# Power_Distribution_2021_9V.net
KiCad netlist of a schematic drawn in Altium Designer
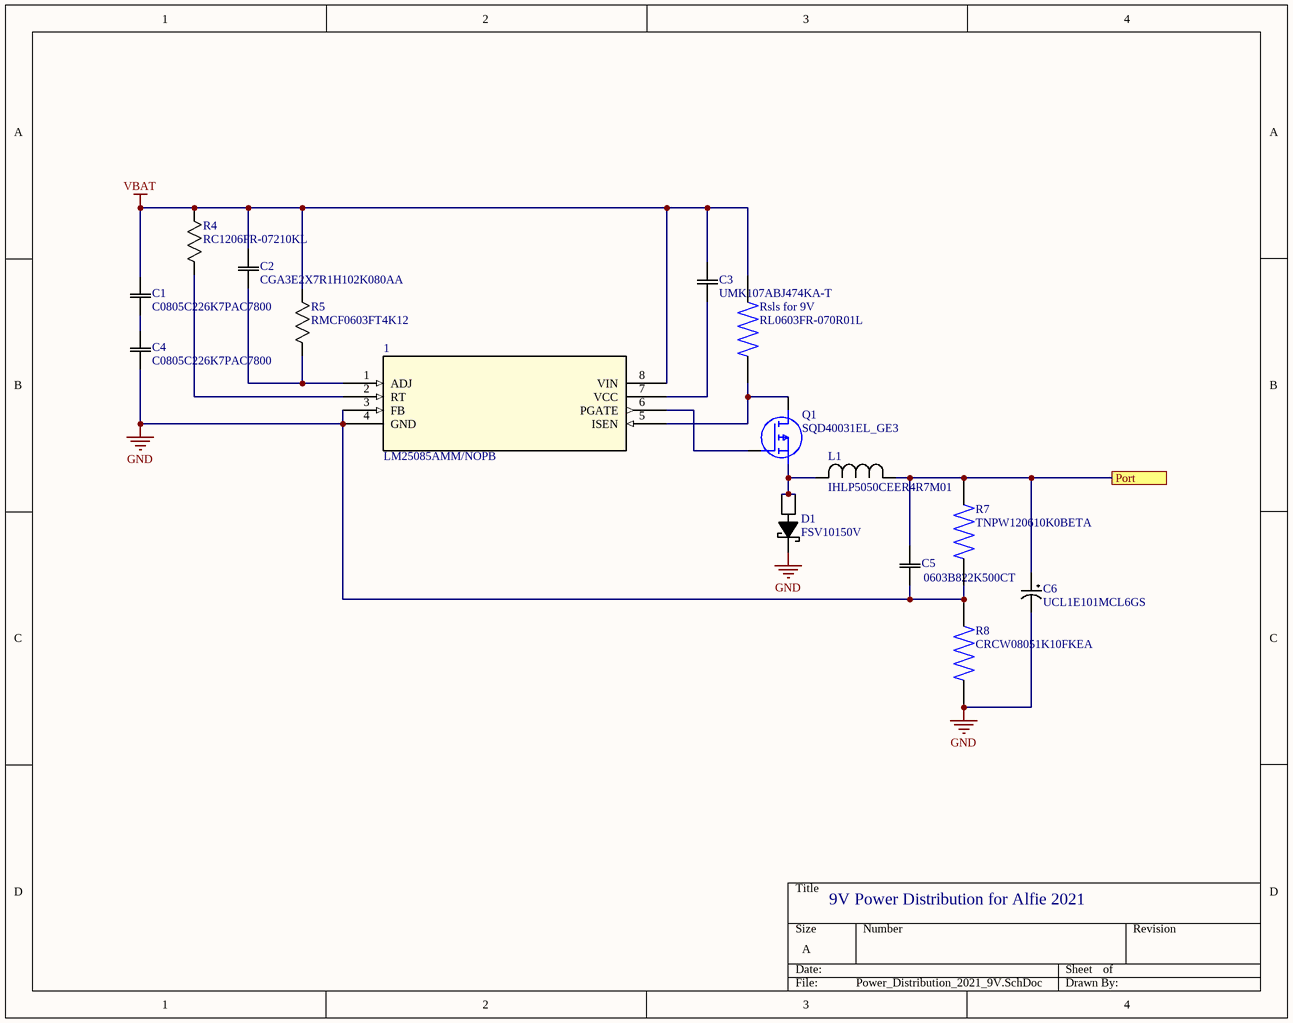
[diagram p0: Power_Distribution_2021_9V.SchDoc]

(export (version "E")
  (design (tool "Eeschema 10.0.6"))
  (components
    (comp (ref "1")
      (value "LM25085AMM/NOPB")
      (footprint "MUA08A")
      (description "IC REG CTRLR BUCK 8VSSOP")
      (fields (field (name "COPYRIGHT") "Copyright (C) 2021 Accelerated Designs. All rights reserved"))
      (libsource (lib "Power_Distribution") (part "LM25085AMM/NOPB"))
    )
    (comp (ref "C1")
      (value "C0805C226K7PAC7800")
      (footprint "SnapEDApcb:CAPC2012X140N")
      (description "22µF ±10% 4V Ceramic Capacitor X5R 0805 _2012 Metric")
      (fields (field (name "MF") "KEMET"))
      (libsource (lib "Power_Distribution") (part "C0805C226K7PAC7800"))
    )
    (comp (ref "C2")
      (value "CGA3E2X7R1H102K080AA")
      (footprint "CAP_1608_TDK")
      (description "CAP CER 1000PF 50V X7R 0603")
      (fields (field (name "COPYRIGHT") "Copyright (C) 2021 Accelerated Designs. All rights reserved"))
      (libsource (lib "Power_Distribution") (part "CGA3E2X7R1H102K080AA"))
    )
    (comp (ref "C3")
      (value "UMK107ABJ474KA-T")
      (footprint "cap_UMK107ABJ474KA-T_TAY")
      (description "CAP CER 0.47UF 50V X5R 0603")
      (fields (field (name "COPYRIGHT") "Copyright (C) 2018 Accelerated Designs. All rights reserved"))
      (libsource (lib "Power_Distribution") (part "UMK107ABJ474KA-T"))
    )
    (comp (ref "C4")
      (value "C0805C226K7PAC7800")
      (footprint "SnapEDApcb:CAPC2012X140N")
      (description "22µF ±10% 4V Ceramic Capacitor X5R 0805 _2012 Metric")
      (fields (field (name "MF") "KEMET"))
      (libsource (lib "Power_Distribution") (part "C0805C226K7PAC7800"))
    )
    (comp (ref "C5")
      (value "0603B822K500CT")
      (footprint "CAP_0603_S_WAL")
      (description "CAP CER 8200PF 50V X7R 0603")
      (fields (field (name "COPYRIGHT") "Copyright (C) 2021 Accelerated Designs. All rights reserved"))
      (libsource (lib "Power_Distribution") (part "0603B822K500CT"))
    )
    (comp (ref "C6")
      (value "UCL1E101MCL6GS")
      (footprint "U2-O_NCH")
      (description "CAP ALUM 100UF 20% 25V SMD")
      (fields (field (name "COPYRIGHT") "Copyright (C) 2021 Accelerated Designs. All rights reserved"))
      (libsource (lib "Power_Distribution") (part "UCL1E101MCL6GS"))
    )
    (comp (ref "D1")
      (value "FSV10150V")
      (footprint "TO-277_3L")
      (description "DIODE SCHOTTKY 150V 10A TO277-3")
      (libsource (lib "Power_Distribution") (part "FSV10150V"))
    )
    (comp (ref "L1")
      (value "IHLP5050CEER4R7M01")
      (footprint "IND_IHLP-5050CE_VIS")
      (description "FIXED IND 4.7UH 10A 15 MOHM SMD")
      (fields (field (name "COPYRIGHT") "Copyright (C) 2021 Accelerated Designs. All rights reserved"))
      (libsource (lib "Power_Distribution") (part "IHLP5050CEER4R7M01"))
    )
    (comp (ref "Q1")
      (value "SQD40031EL_GE3")
      (footprint "Power_Distribution:SQD40031EL_GE3")
      (description "MOSFET (P-Channel)")
      (libsource (lib "Power_Distribution") (part "SQD40031EL_GE3"))
    )
    (comp (ref "R4")
      (value "RC1206FR-07210KL")
      (footprint "RC1206N_YAG")
      (description "RES SMD 210K OHM 1% 1/4W 1206")
      (fields (field (name "COPYRIGHT") "Copyright (C) 2021 Accelerated Designs. All rights reserved"))
      (libsource (lib "Power_Distribution") (part "RC1206FR-07210KL"))
    )
    (comp (ref "R5")
      (value "RMCF0603FT4K12")
      (footprint "STA_RMCF0603_STP")
      (description "RES 4.12K OHM 1% 1/10W 0603")
      (fields (field (name "COPYRIGHT") "Copyright (C) 2021 Accelerated Designs. All rights reserved"))
      (libsource (lib "Power_Distribution") (part "RMCF0603FT4K12"))
    )
    (comp (ref "R7")
      (value "TNPW120610K0BETA")
      (footprint "RESC3216X65N:RESC3216X65N")
      (description "Res Thin Film 1206 10K Ohm 0.1% 0.25W(1/4W) ?25ppm/C Molded SMD T/R")
      (libsource (lib "Power_Distribution") (part "TNPW120610K0BETA"))
    )
    (comp (ref "R8")
      (value "CRCW08051K10FKEA")
      (footprint "RESC2012X50N:RESC2012X50N")
      (description "D12/Crcw0805 100 1K1 1% Et1 E3")
      (libsource (lib "Power_Distribution") (part "CRCW08051K10FKEA"))
    )
    (comp (ref "Rsls for 9V")
      (value "RL0603FR-070R01L")
      (footprint "RESC1608X55N")
      (description ".01 OHM 1% 1/10W")
      (libsource (lib "Power_Distribution") (part "RL0603FR-070R01L"))
    )
  )
  (nets
    (net (code "1") (name "/Port") (class "Default")
      (node (ref "C5") (pin "2") (pinfunction "2_2") (pintype "passive"))
      (node (ref "C6") (pin "1") (pinfunction "1_1") (pintype "passive"))
      (node (ref "L1") (pin "1") (pinfunction "1_1") (pintype "passive"))
      (node (ref "R7") (pin "2") (pinfunction "2_2") (pintype "passive"))
    )
    (net (code "2") (name "GND") (class "Default")
      (node (ref "1") (pin "3") (pinfunction "FB_3") (pintype "input"))
      (node (ref "1") (pin "4") (pinfunction "GND_4") (pintype "power_in"))
      (node (ref "C4") (pin "1") (pinfunction "1_1") (pintype "passive"))
      (node (ref "C5") (pin "1") (pinfunction "1_1") (pintype "passive"))
      (node (ref "C6") (pin "2") (pinfunction "2_2") (pintype "passive"))
      (node (ref "D1") (pin "2") (pinfunction "2_2") (pintype "passive"))
      (node (ref "R7") (pin "1") (pinfunction "1_1") (pintype "passive"))
      (node (ref "R8") (pin "1") (pinfunction "1_1") (pintype "passive"))
      (node (ref "R8") (pin "2") (pinfunction "2_2") (pintype "passive"))
    )
    (net (code "3") (name "Net-(1-ADJ)") (class "Default")
      (node (ref "1") (pin "1") (pinfunction "ADJ_1") (pintype "input"))
      (node (ref "C2") (pin "1") (pinfunction "1_1") (pintype "passive"))
      (node (ref "R5") (pin "1") (pinfunction "1_1") (pintype "passive"))
    )
    (net (code "4") (name "Net-(1-ISEN)") (class "Default")
      (node (ref "1") (pin "5") (pinfunction "ISEN_5") (pintype "input"))
      (node (ref "Q1") (pin "3") (pinfunction "D_3") (pintype "passive"))
      (node (ref "Rsls for 9V") (pin "1") (pinfunction "1_1") (pintype "passive"))
    )
    (net (code "5") (name "Net-(1-PGATE)") (class "Default")
      (node (ref "1") (pin "6") (pinfunction "PGATE_6") (pintype "output"))
      (node (ref "Q1") (pin "1") (pinfunction "G_1") (pintype "passive"))
    )
    (net (code "6") (name "Net-(1-RT)") (class "Default")
      (node (ref "1") (pin "2") (pinfunction "RT_2") (pintype "input"))
      (node (ref "R4") (pin "2") (pinfunction "2_2") (pintype "passive"))
    )
    (net (code "7") (name "Net-(1-VCC)") (class "Default")
      (node (ref "1") (pin "7") (pinfunction "VCC_7") (pintype "power_in"))
      (node (ref "C3") (pin "2") (pinfunction "2_2") (pintype "passive"))
    )
    (net (code "8") (name "Net-(C1-Pad1)") (class "Default")
      (node (ref "C1") (pin "1") (pinfunction "1_1") (pintype "passive"))
      (node (ref "C4") (pin "2") (pinfunction "2_2") (pintype "passive"))
    )
    (net (code "9") (name "Net-(Q1-S)") (class "Default")
      (node (ref "D1") (pin "0") (pinfunction "0_0") (pintype "passive"))
      (node (ref "D1") (pin "1") (pinfunction "1_1") (pintype "passive"))
      (node (ref "L1") (pin "2") (pinfunction "2_2") (pintype "passive"))
      (node (ref "Q1") (pin "2") (pinfunction "S_2") (pintype "passive"))
    )
    (net (code "10") (name "VBAT") (class "Default")
      (node (ref "1") (pin "8") (pinfunction "VIN_8") (pintype "power_in"))
      (node (ref "C1") (pin "2") (pinfunction "2_2") (pintype "passive"))
      (node (ref "C2") (pin "2") (pinfunction "2_2") (pintype "passive"))
      (node (ref "C3") (pin "1") (pinfunction "1_1") (pintype "passive"))
      (node (ref "R4") (pin "1") (pinfunction "1_1") (pintype "passive"))
      (node (ref "R5") (pin "2") (pinfunction "2_2") (pintype "passive"))
      (node (ref "Rsls for 9V") (pin "2") (pinfunction "2_2") (pintype "passive"))
    )
  )
)
